# board.net
KiCad netlist of a schematic drawn in EAGLE
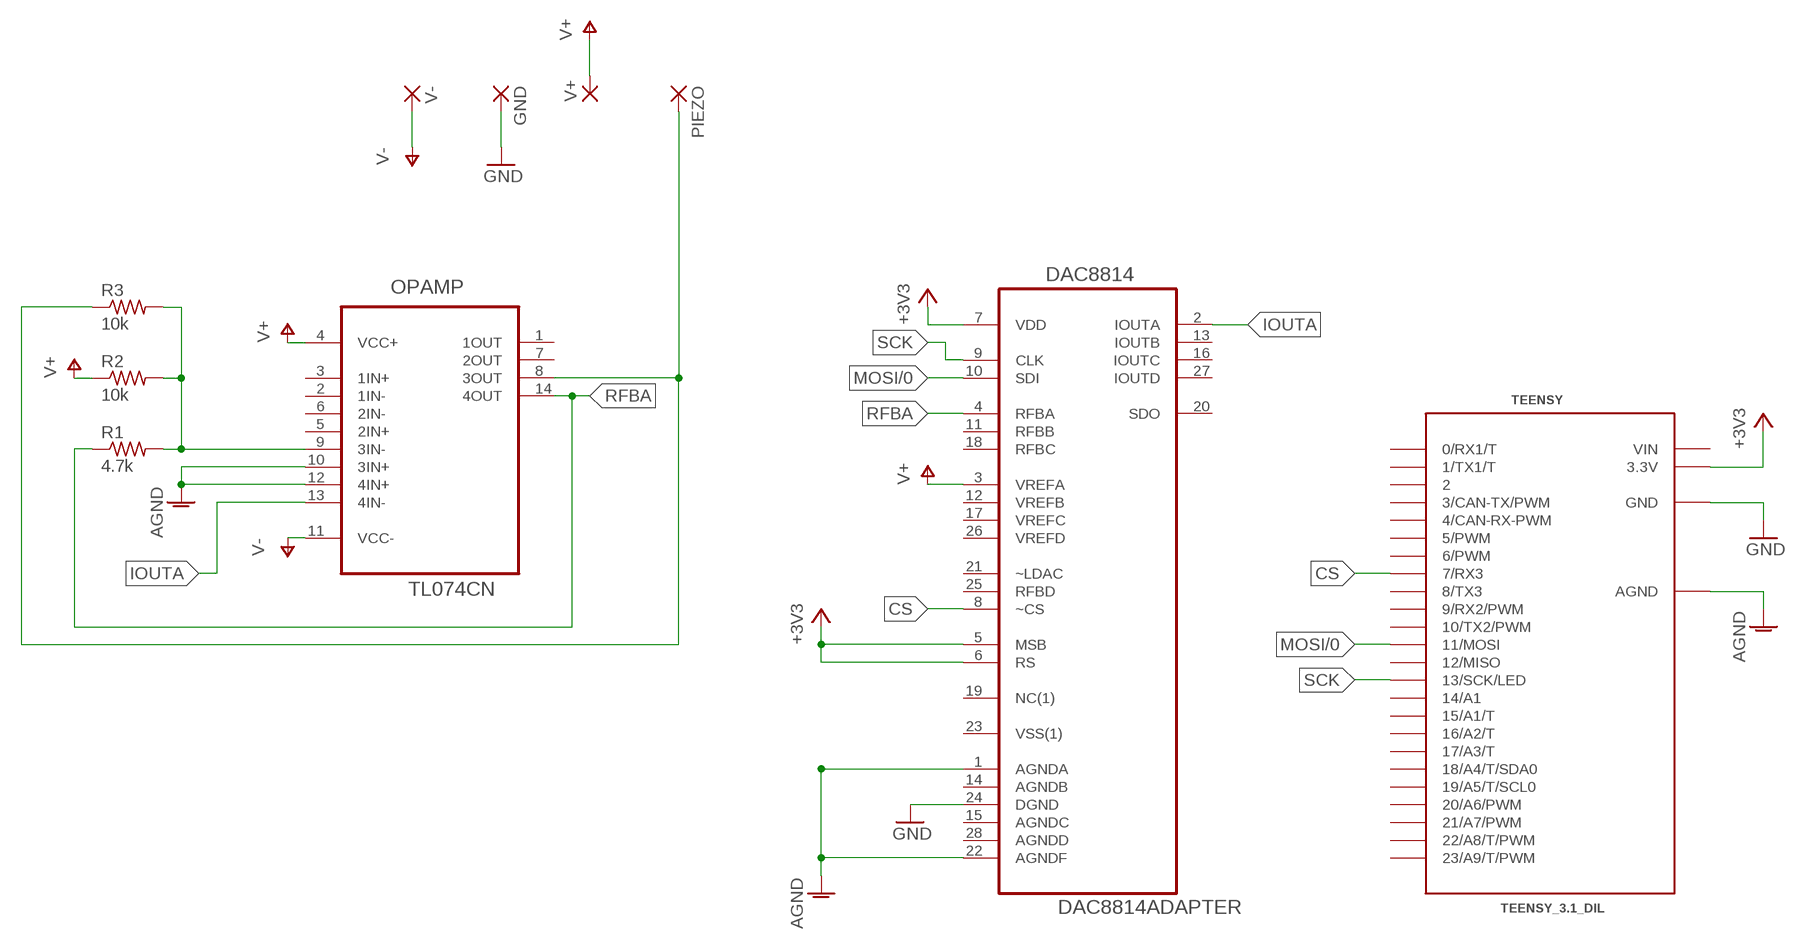
[diagram p0: schematic, sheet 1]

(export (version "E")
  (design (tool "Eeschema 10.0.6"))
  (components
    (comp (ref "DAC8814")
      (value "DAC8814ADAPTER")
      (footprint "eagle-import:DIL28-6")
      (libsource (lib "eagle-import") (part "DAC8814ADAPTER"))
    )
    (comp (ref "GND")
      (value "1,6/0,8")
      (footprint "eagle-import:1,6_0,8")
      (libsource (lib "eagle-import") (part "1,6/0,8"))
    )
    (comp (ref "OPAMP")
      (value "TL074CN")
      (footprint "eagle-import:DIP254P762X508-14")
      (libsource (lib "eagle-import") (part "TL074CN"))
    )
    (comp (ref "PIEZO")
      (value "1,6/0,8")
      (footprint "eagle-import:1,6_0,8")
      (libsource (lib "eagle-import") (part "1,6/0,8"))
    )
    (comp (ref "R1")
      (value "4.7k")
      (footprint "eagle-import:0204_7")
      (libsource (lib "eagle-import") (part "R-US_0204/7"))
    )
    (comp (ref "R2")
      (value "10k")
      (footprint "eagle-import:0204_5")
      (libsource (lib "eagle-import") (part "R-US_0204/5"))
    )
    (comp (ref "R3")
      (value "10k")
      (footprint "eagle-import:0204_5")
      (libsource (lib "eagle-import") (part "R-US_0204/5"))
    )
    (comp (ref "TEENSY")
      (value "TEENSY_3.1_DIL")
      (footprint "eagle-import:TEENSY3-DIL")
      (libsource (lib "eagle-import") (part "TEENSY_3.1_DIL"))
    )
    (comp (ref "V+")
      (value "1,6/0,8")
      (footprint "eagle-import:1,6_0,8")
      (libsource (lib "eagle-import") (part "1,6/0,8"))
    )
    (comp (ref "V-")
      (value "1,6/0,8")
      (footprint "eagle-import:1,6_0,8")
      (libsource (lib "eagle-import") (part "1,6/0,8"))
    )
  )
  (nets
    (net (code "1") (name "+3V3") (class "Default")
      (node (ref "DAC8814") (pin "5") (pinfunction "MSB_5") (pintype "input"))
      (node (ref "DAC8814") (pin "6") (pinfunction "RS_6") (pintype "input"))
      (node (ref "DAC8814") (pin "7") (pinfunction "VDD_7") (pintype "power_in"))
      (node (ref "TEENSY") (pin "3.3V") (pinfunction "3.3V_3.3V") (pintype "power_in"))
    )
    (net (code "2") (name "/VIN") (class "Default")
      (node (ref "TEENSY") (pin "VIN") (pinfunction "VIN_VIN") (pintype "power_in"))
    )
    (net (code "3") (name "AGND") (class "Default")
      (node (ref "DAC8814") (pin "1") (pinfunction "AGNDA_1") (pintype "passive"))
      (node (ref "DAC8814") (pin "22") (pinfunction "AGNDF_22") (pintype "passive"))
      (node (ref "OPAMP") (pin "10") (pinfunction "3IN+_10") (pintype "input"))
      (node (ref "OPAMP") (pin "12") (pinfunction "4IN+_12") (pintype "input"))
      (node (ref "TEENSY") (pin "AGND") (pinfunction "AGND_AGND") (pintype "power_in"))
    )
    (net (code "4") (name "CS") (class "Default")
      (node (ref "DAC8814") (pin "8") (pinfunction "~{CS}_8") (pintype "input"))
      (node (ref "TEENSY") (pin "7") (pinfunction "7/RX3_7") (pintype "bidirectional"))
    )
    (net (code "5") (name "GND") (class "Default")
      (node (ref "DAC8814") (pin "24") (pinfunction "DGND_24") (pintype "passive"))
      (node (ref "GND") (pin "1") (pinfunction "P_1") (pintype "passive"))
      (node (ref "TEENSY") (pin "GND") (pinfunction "GND_GND") (pintype "power_in"))
    )
    (net (code "6") (name "IOUTA") (class "Default")
      (node (ref "DAC8814") (pin "2") (pinfunction "IOUTA_2") (pintype "output"))
      (node (ref "OPAMP") (pin "13") (pinfunction "4IN-_13") (pintype "input"))
    )
    (net (code "7") (name "MOSI{slash}0") (class "Default")
      (node (ref "DAC8814") (pin "10") (pinfunction "SDI_10") (pintype "input"))
      (node (ref "TEENSY") (pin "11") (pinfunction "11/MOSI_11") (pintype "bidirectional"))
    )
    (net (code "8") (name "Net-(OPAMP-3IN-)") (class "Default")
      (node (ref "OPAMP") (pin "9") (pinfunction "3IN-_9") (pintype "input"))
      (node (ref "R1") (pin "2") (pinfunction "2_2") (pintype "passive"))
      (node (ref "R2") (pin "2") (pinfunction "2_2") (pintype "passive"))
      (node (ref "R3") (pin "2") (pinfunction "2_2") (pintype "passive"))
    )
    (net (code "9") (name "Net-(OPAMP-3OUT)") (class "Default")
      (node (ref "OPAMP") (pin "8") (pinfunction "3OUT_8") (pintype "output"))
      (node (ref "PIEZO") (pin "1") (pinfunction "P_1") (pintype "passive"))
      (node (ref "R3") (pin "1") (pinfunction "1_1") (pintype "passive"))
    )
    (net (code "10") (name "RFBA") (class "Default")
      (node (ref "DAC8814") (pin "4") (pinfunction "RFBA_4") (pintype "input"))
      (node (ref "OPAMP") (pin "14") (pinfunction "4OUT_14") (pintype "output"))
      (node (ref "R1") (pin "1") (pinfunction "1_1") (pintype "passive"))
    )
    (net (code "11") (name "SCK") (class "Default")
      (node (ref "DAC8814") (pin "9") (pinfunction "CLK_9") (pintype "input"))
      (node (ref "TEENSY") (pin "13") (pinfunction "13/SCK/LED_13") (pintype "bidirectional"))
    )
    (net (code "12") (name "V+") (class "Default")
      (node (ref "DAC8814") (pin "3") (pinfunction "VREFA_3") (pintype "input"))
      (node (ref "OPAMP") (pin "4") (pinfunction "VCC+_4") (pintype "power_in"))
      (node (ref "R2") (pin "1") (pinfunction "1_1") (pintype "passive"))
      (node (ref "V+") (pin "1") (pinfunction "P_1") (pintype "passive"))
    )
    (net (code "13") (name "V-") (class "Default")
      (node (ref "OPAMP") (pin "11") (pinfunction "VCC-_11") (pintype "power_in"))
      (node (ref "V-") (pin "1") (pinfunction "P_1") (pintype "passive"))
    )
    (net (code "14") (name "unconnected-(DAC8814-AGNDB-Pad14)") (class "Default")
      (node (ref "DAC8814") (pin "14") (pinfunction "AGNDB_14") (pintype "passive"))
    )
    (net (code "15") (name "unconnected-(DAC8814-AGNDC-Pad15)") (class "Default")
      (node (ref "DAC8814") (pin "15") (pinfunction "AGNDC_15") (pintype "passive"))
    )
    (net (code "16") (name "unconnected-(DAC8814-AGNDD-Pad28)") (class "Default")
      (node (ref "DAC8814") (pin "28") (pinfunction "AGNDD_28") (pintype "passive"))
    )
    (net (code "17") (name "unconnected-(DAC8814-IOUTB-Pad13)") (class "Default")
      (node (ref "DAC8814") (pin "13") (pinfunction "IOUTB_13") (pintype "output"))
    )
    (net (code "18") (name "unconnected-(DAC8814-IOUTC-Pad16)") (class "Default")
      (node (ref "DAC8814") (pin "16") (pinfunction "IOUTC_16") (pintype "output"))
    )
    (net (code "19") (name "unconnected-(DAC8814-IOUTD-Pad27)") (class "Default")
      (node (ref "DAC8814") (pin "27") (pinfunction "IOUTD_27") (pintype "output"))
    )
    (net (code "20") (name "unconnected-(DAC8814-NC(1)-Pad19)") (class "Default")
      (node (ref "DAC8814") (pin "19") (pinfunction "NC(1)_19") (pintype "no_connect"))
    )
    (net (code "21") (name "unconnected-(DAC8814-RFBB-Pad11)") (class "Default")
      (node (ref "DAC8814") (pin "11") (pinfunction "RFBB_11") (pintype "input"))
    )
    (net (code "22") (name "unconnected-(DAC8814-RFBC-Pad18)") (class "Default")
      (node (ref "DAC8814") (pin "18") (pinfunction "RFBC_18") (pintype "input"))
    )
    (net (code "23") (name "unconnected-(DAC8814-RFBD-Pad25)") (class "Default")
      (node (ref "DAC8814") (pin "25") (pinfunction "RFBD_25") (pintype "input"))
    )
    (net (code "24") (name "unconnected-(DAC8814-SDO-Pad20)") (class "Default")
      (node (ref "DAC8814") (pin "20") (pinfunction "SDO_20") (pintype "output"))
    )
    (net (code "25") (name "unconnected-(DAC8814-VREFB-Pad12)") (class "Default")
      (node (ref "DAC8814") (pin "12") (pinfunction "VREFB_12") (pintype "input"))
    )
    (net (code "26") (name "unconnected-(DAC8814-VREFC-Pad17)") (class "Default")
      (node (ref "DAC8814") (pin "17") (pinfunction "VREFC_17") (pintype "input"))
    )
    (net (code "27") (name "unconnected-(DAC8814-VREFD-Pad26)") (class "Default")
      (node (ref "DAC8814") (pin "26") (pinfunction "VREFD_26") (pintype "input"))
    )
    (net (code "28") (name "unconnected-(DAC8814-VSS(1)-Pad23)") (class "Default")
      (node (ref "DAC8814") (pin "23") (pinfunction "VSS(1)_23") (pintype "passive"))
    )
    (net (code "29") (name "unconnected-(DAC8814-~{LDAC}-Pad21)") (class "Default")
      (node (ref "DAC8814") (pin "21") (pinfunction "~{LDAC}_21") (pintype "input"))
    )
    (net (code "30") (name "unconnected-(OPAMP-1IN+-Pad3)") (class "Default")
      (node (ref "OPAMP") (pin "3") (pinfunction "1IN+_3") (pintype "input"))
    )
    (net (code "31") (name "unconnected-(OPAMP-1IN--Pad2)") (class "Default")
      (node (ref "OPAMP") (pin "2") (pinfunction "1IN-_2") (pintype "input"))
    )
    (net (code "32") (name "unconnected-(OPAMP-1OUT-Pad1)") (class "Default")
      (node (ref "OPAMP") (pin "1") (pinfunction "1OUT_1") (pintype "output"))
    )
    (net (code "33") (name "unconnected-(OPAMP-2IN+-Pad5)") (class "Default")
      (node (ref "OPAMP") (pin "5") (pinfunction "2IN+_5") (pintype "input"))
    )
    (net (code "34") (name "unconnected-(OPAMP-2IN--Pad6)") (class "Default")
      (node (ref "OPAMP") (pin "6") (pinfunction "2IN-_6") (pintype "input"))
    )
    (net (code "35") (name "unconnected-(OPAMP-2OUT-Pad7)") (class "Default")
      (node (ref "OPAMP") (pin "7") (pinfunction "2OUT_7") (pintype "output"))
    )
    (net (code "36") (name "unconnected-(TEENSY-0{slash}RX1{slash}T-Pad0)") (class "Default")
      (node (ref "TEENSY") (pin "0") (pinfunction "0/RX1/T_0") (pintype "bidirectional"))
    )
    (net (code "37") (name "unconnected-(TEENSY-1{slash}TX1{slash}T-Pad1)") (class "Default")
      (node (ref "TEENSY") (pin "1") (pinfunction "1/TX1/T_1") (pintype "bidirectional"))
    )
    (net (code "38") (name "unconnected-(TEENSY-3{slash}CAN-TX{slash}PWM-Pad3)") (class "Default")
      (node (ref "TEENSY") (pin "3") (pinfunction "3/CAN-TX/PWM_3") (pintype "bidirectional"))
    )
    (net (code "39") (name "unconnected-(TEENSY-4{slash}CAN-RX-PWM-Pad4)") (class "Default")
      (node (ref "TEENSY") (pin "4") (pinfunction "4/CAN-RX-PWM_4") (pintype "bidirectional"))
    )
    (net (code "40") (name "unconnected-(TEENSY-5{slash}PWM-Pad5)") (class "Default")
      (node (ref "TEENSY") (pin "5") (pinfunction "5/PWM_5") (pintype "bidirectional"))
    )
    (net (code "41") (name "unconnected-(TEENSY-6{slash}PWM-Pad6)") (class "Default")
      (node (ref "TEENSY") (pin "6") (pinfunction "6/PWM_6") (pintype "bidirectional"))
    )
    (net (code "42") (name "unconnected-(TEENSY-8{slash}TX3-Pad8)") (class "Default")
      (node (ref "TEENSY") (pin "8") (pinfunction "8/TX3_8") (pintype "bidirectional"))
    )
    (net (code "43") (name "unconnected-(TEENSY-9{slash}RX2{slash}PWM-Pad9)") (class "Default")
      (node (ref "TEENSY") (pin "9") (pinfunction "9/RX2/PWM_9") (pintype "bidirectional"))
    )
    (net (code "44") (name "unconnected-(TEENSY-10{slash}TX2{slash}PWM-Pad10)") (class "Default")
      (node (ref "TEENSY") (pin "10") (pinfunction "10/TX2/PWM_10") (pintype "bidirectional"))
    )
    (net (code "45") (name "unconnected-(TEENSY-12{slash}MISO-Pad12)") (class "Default")
      (node (ref "TEENSY") (pin "12") (pinfunction "12/MISO_12") (pintype "bidirectional"))
    )
    (net (code "46") (name "unconnected-(TEENSY-14{slash}A1-Pad14{slash}A0)") (class "Default")
      (node (ref "TEENSY") (pin "14/A0") (pinfunction "14/A1_14/A0") (pintype "bidirectional"))
    )
    (net (code "47") (name "unconnected-(TEENSY-15{slash}A1{slash}T-Pad15{slash}A1)") (class "Default")
      (node (ref "TEENSY") (pin "15/A1") (pinfunction "15/A1/T_15/A1") (pintype "bidirectional"))
    )
    (net (code "48") (name "unconnected-(TEENSY-16{slash}A2{slash}T-Pad16{slash}A2)") (class "Default")
      (node (ref "TEENSY") (pin "16/A2") (pinfunction "16/A2/T_16/A2") (pintype "bidirectional"))
    )
    (net (code "49") (name "unconnected-(TEENSY-17{slash}A3{slash}T-Pad17{slash}A3)") (class "Default")
      (node (ref "TEENSY") (pin "17/A3") (pinfunction "17/A3/T_17/A3") (pintype "bidirectional"))
    )
    (net (code "50") (name "unconnected-(TEENSY-18{slash}A4{slash}T{slash}SDA0-Pad18{slash}A4)") (class "Default")
      (node (ref "TEENSY") (pin "18/A4") (pinfunction "18/A4/T/SDA0_18/A4") (pintype "bidirectional"))
    )
    (net (code "51") (name "unconnected-(TEENSY-19{slash}A5{slash}T{slash}SCL0-Pad19{slash}A5)") (class "Default")
      (node (ref "TEENSY") (pin "19/A5") (pinfunction "19/A5/T/SCL0_19/A5") (pintype "bidirectional"))
    )
    (net (code "52") (name "unconnected-(TEENSY-20{slash}A6{slash}PWM-Pad20{slash}A6)") (class "Default")
      (node (ref "TEENSY") (pin "20/A6") (pinfunction "20/A6/PWM_20/A6") (pintype "bidirectional"))
    )
    (net (code "53") (name "unconnected-(TEENSY-21{slash}A7{slash}PWM-Pad21{slash}A7)") (class "Default")
      (node (ref "TEENSY") (pin "21/A7") (pinfunction "21/A7/PWM_21/A7") (pintype "bidirectional"))
    )
    (net (code "54") (name "unconnected-(TEENSY-22{slash}A8{slash}T{slash}PWM-Pad22{slash}A8)") (class "Default")
      (node (ref "TEENSY") (pin "22/A8") (pinfunction "22/A8/T/PWM_22/A8") (pintype "bidirectional"))
    )
    (net (code "55") (name "unconnected-(TEENSY-23{slash}A9{slash}T{slash}PWM-Pad23{slash}A9)") (class "Default")
      (node (ref "TEENSY") (pin "23/A9") (pinfunction "23/A9/T/PWM_23/A9") (pintype "bidirectional"))
    )
    (net (code "56") (name "unconnected-(TEENSY-Pad2)") (class "Default")
      (node (ref "TEENSY") (pin "2") (pinfunction "2_2") (pintype "bidirectional"))
    )
  )
)
